# 770LCM.net
KiCad netlist of a schematic drawn in EAGLE
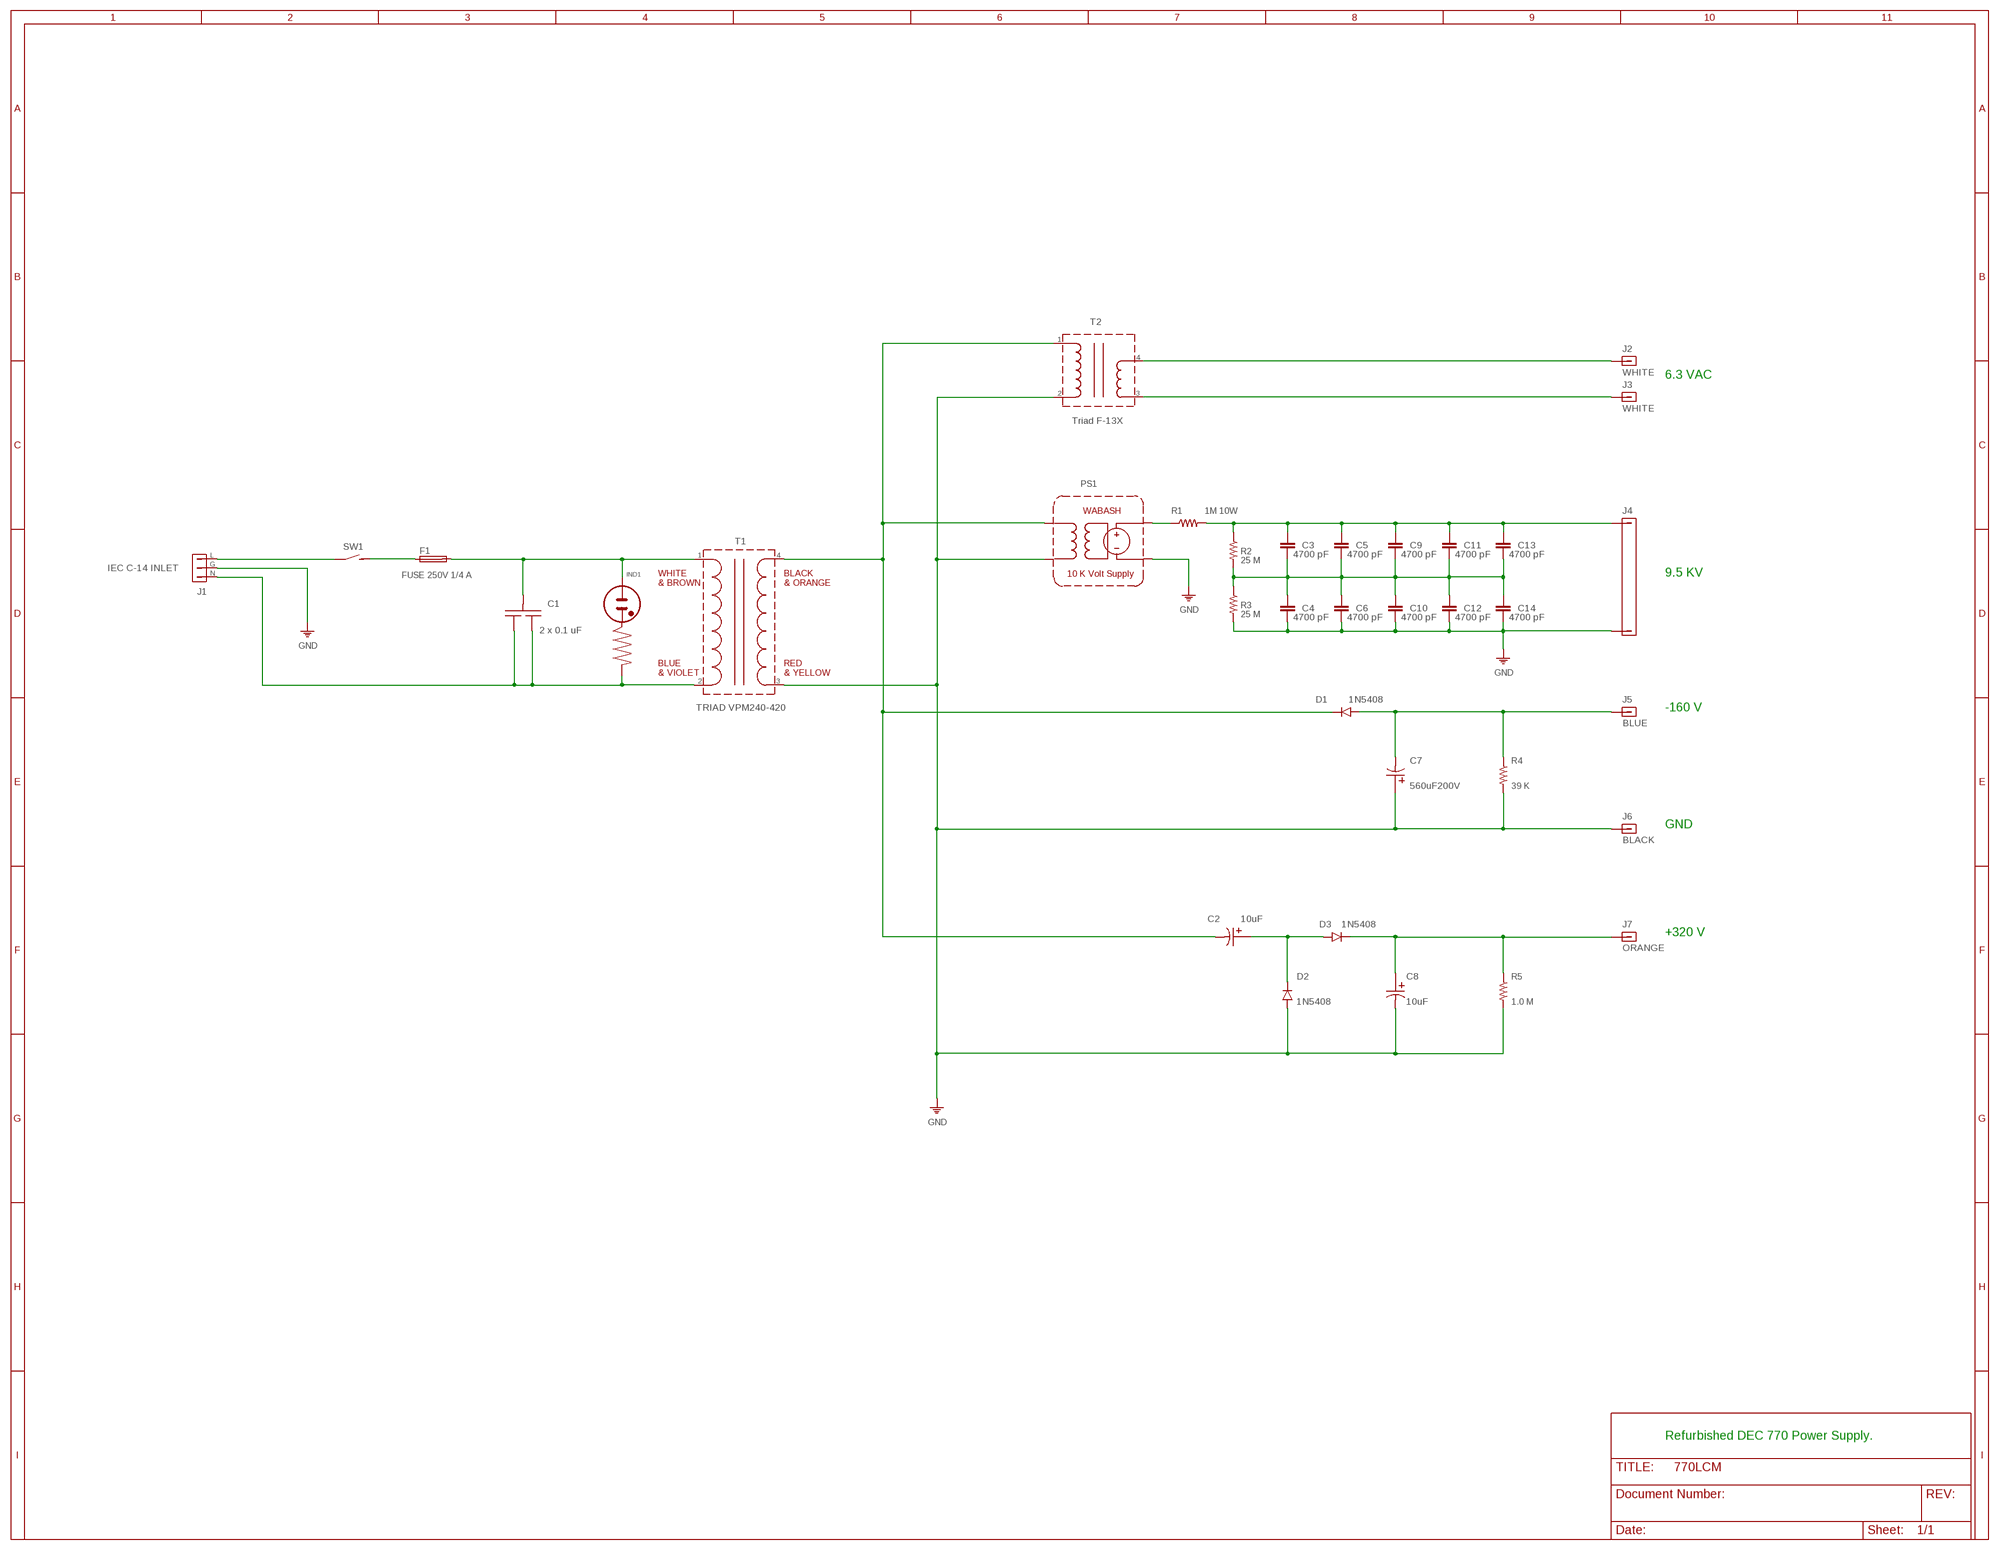
[diagram p0: schematic, sheet 1]

(export (version "E")
  (design (tool "Eeschema 10.0.6"))
  (components
    (comp (ref "C1")
      (value "2 x 0.1 uF")
      (footprint "eagle-import:THREE-PIN")
      (libsource (lib "eagle-import") (part "SPLIT-CAP"))
    )
    (comp (ref "C2")
      (value "10uF")
      (footprint "eagle-import:AXIAL10UF400V")
      (libsource (lib "eagle-import") (part "CAP400V10UF"))
    )
    (comp (ref "C3")
      (value "4700 pF")
      (footprint "eagle-import:C2.5")
      (libsource (lib "eagle-import") (part "C-0.1"))
    )
    (comp (ref "C4")
      (value "4700 pF")
      (footprint "eagle-import:C2.5")
      (libsource (lib "eagle-import") (part "C-0.1"))
    )
    (comp (ref "C5")
      (value "4700 pF")
      (footprint "eagle-import:C2.5")
      (libsource (lib "eagle-import") (part "C-0.1"))
    )
    (comp (ref "C6")
      (value "4700 pF")
      (footprint "eagle-import:C2.5")
      (libsource (lib "eagle-import") (part "C-0.1"))
    )
    (comp (ref "C7")
      (value "560uF200V")
      (footprint "eagle-import:WIREDCAP")
      (libsource (lib "eagle-import") (part "WIREDCAP"))
    )
    (comp (ref "C8")
      (value "10uF")
      (footprint "eagle-import:AXIAL10UF400V")
      (libsource (lib "eagle-import") (part "CAP400V10UF"))
    )
    (comp (ref "C9")
      (value "4700 pF")
      (footprint "eagle-import:C2.5")
      (libsource (lib "eagle-import") (part "C-0.1"))
    )
    (comp (ref "C10")
      (value "4700 pF")
      (footprint "eagle-import:C2.5")
      (libsource (lib "eagle-import") (part "C-0.1"))
    )
    (comp (ref "C11")
      (value "4700 pF")
      (footprint "eagle-import:C2.5")
      (libsource (lib "eagle-import") (part "C-0.1"))
    )
    (comp (ref "C12")
      (value "4700 pF")
      (footprint "eagle-import:C2.5")
      (libsource (lib "eagle-import") (part "C-0.1"))
    )
    (comp (ref "C13")
      (value "4700 pF")
      (footprint "eagle-import:C2.5")
      (libsource (lib "eagle-import") (part "C-0.1"))
    )
    (comp (ref "C14")
      (value "4700 pF")
      (footprint "eagle-import:C2.5")
      (libsource (lib "eagle-import") (part "C-0.1"))
    )
    (comp (ref "D1")
      (value "1N5408")
      (footprint "eagle-import:DO-201AD")
      (libsource (lib "eagle-import") (part "1N5408"))
    )
    (comp (ref "D2")
      (value "1N5408")
      (footprint "eagle-import:DO-201AD")
      (libsource (lib "eagle-import") (part "1N5408"))
    )
    (comp (ref "D3")
      (value "1N5408")
      (footprint "eagle-import:DO-201AD")
      (libsource (lib "eagle-import") (part "1N5408"))
    )
    (comp (ref "F1")
      (value "FUSE 250V 1/4 A")
      (footprint "eagle-import:FUSE_HOLDER_SCHURTER-FAS")
      (fields (field (name "MPN") "0031.3501"))
      (libsource (lib "eagle-import") (part "FUSEFAS"))
    )
    (comp (ref "IND1")
      (value "NEON_INDICATOR")
      (footprint "eagle-import:TWO-PIN")
      (libsource (lib "eagle-import") (part "NEON_INDICATOR"))
    )
    (comp (ref "J1")
      (value "IEC C-14 INLET")
      (footprint "eagle-import:IEC_CONNECTOR")
      (libsource (lib "eagle-import") (part "IEC-C14"))
    )
    (comp (ref "J2")
      (value "WHITE")
      (footprint "eagle-import:AWG18")
      (libsource (lib "eagle-import") (part "BANANA_JACK"))
    )
    (comp (ref "J3")
      (value "WHITE")
      (footprint "eagle-import:AWG18")
      (libsource (lib "eagle-import") (part "BANANA_JACK"))
    )
    (comp (ref "J4")
      (value "HV_CONN")
      (footprint "eagle-import:TWO-PIN")
      (libsource (lib "eagle-import") (part "HV_CONN"))
    )
    (comp (ref "J5")
      (value "BLUE")
      (footprint "eagle-import:AWG18")
      (libsource (lib "eagle-import") (part "BANANA_JACK"))
    )
    (comp (ref "J6")
      (value "BLACK")
      (footprint "eagle-import:AWG18")
      (libsource (lib "eagle-import") (part "BANANA_JACK"))
    )
    (comp (ref "J7")
      (value "ORANGE")
      (footprint "eagle-import:AWG18")
      (libsource (lib "eagle-import") (part "BANANA_JACK"))
    )
    (comp (ref "PS1")
      (value "WABASH-HV")
      (footprint "eagle-import:TRANSFORMER")
      (libsource (lib "eagle-import") (part "WABASH-HV"))
    )
    (comp (ref "R1")
      (value "1M 10W")
      (footprint "eagle-import:0207_10")
      (libsource (lib "eagle-import") (part "RES-H"))
    )
    (comp (ref "R2")
      (value "25 M")
      (footprint "eagle-import:0207_10")
      (libsource (lib "eagle-import") (part "RES-V"))
    )
    (comp (ref "R3")
      (value "25 M")
      (footprint "eagle-import:0207_10")
      (libsource (lib "eagle-import") (part "RES-V"))
    )
    (comp (ref "R4")
      (value "39 K")
      (footprint "eagle-import:0207_10")
      (libsource (lib "eagle-import") (part "RES-V"))
    )
    (comp (ref "R5")
      (value "1.0 M")
      (footprint "eagle-import:0207_10")
      (libsource (lib "eagle-import") (part "RES-V"))
    )
    (comp (ref "SW1")
      (value "SWITCH")
      (footprint "eagle-import:SWITCH")
      (libsource (lib "eagle-import") (part "SWITCH"))
    )
    (comp (ref "T1")
      (value "TRIAD VPM240-420")
      (footprint "eagle-import:TRANSFORMER")
      (libsource (lib "eagle-import") (part "TRANSFORMER"))
    )
    (comp (ref "T2")
      (value "Triad F-13X")
      (footprint "eagle-import:TRANSFORMER")
      (libsource (lib "eagle-import") (part "SMALLTRANSFORMER"))
    )
  )
  (nets
    (net (code "1") (name "GND") (class "Default")
      (node (ref "C10") (pin "2") (pinfunction "2_2") (pintype "passive"))
      (node (ref "C12") (pin "2") (pinfunction "2_2") (pintype "passive"))
      (node (ref "C14") (pin "2") (pinfunction "2_2") (pintype "passive"))
      (node (ref "C4") (pin "2") (pinfunction "2_2") (pintype "passive"))
      (node (ref "C6") (pin "2") (pinfunction "2_2") (pintype "passive"))
      (node (ref "C7") (pin "P$1") (pinfunction "1_P$1") (pintype "passive"))
      (node (ref "C8") (pin "P$2") (pinfunction "2_P$2") (pintype "passive"))
      (node (ref "D2") (pin "A") (pinfunction "A_A") (pintype "passive"))
      (node (ref "J1") (pin "G") (pinfunction "G_G") (pintype "passive"))
      (node (ref "J4") (pin "P$2") (pinfunction "L1_P$2") (pintype "passive"))
      (node (ref "J6") (pin "P$1") (pinfunction "L1_P$1") (pintype "passive"))
      (node (ref "PS1") (pin "2") (pinfunction "AC2_2") (pintype "passive"))
      (node (ref "PS1") (pin "3") (pinfunction "GND_3") (pintype "passive"))
      (node (ref "R3") (pin "2") (pinfunction "P$2_2") (pintype "passive"))
      (node (ref "R4") (pin "2") (pinfunction "P$2_2") (pintype "passive"))
      (node (ref "R5") (pin "2") (pinfunction "P$2_2") (pintype "passive"))
      (node (ref "T1") (pin "3") (pinfunction "3_3") (pintype "bidirectional"))
      (node (ref "T2") (pin "2") (pinfunction "2_2") (pintype "bidirectional"))
    )
    (net (code "2") (name "Net-(C1-1)") (class "Default")
      (node (ref "C1") (pin "P$1") (pinfunction "1_P$1") (pintype "passive"))
      (node (ref "C1") (pin "P$2") (pinfunction "2_P$2") (pintype "passive"))
      (node (ref "IND1") (pin "P$2") (pinfunction "A1_P$2") (pintype "passive"))
      (node (ref "J1") (pin "N") (pinfunction "L_N") (pintype "passive"))
      (node (ref "T1") (pin "2") (pinfunction "2_2") (pintype "bidirectional"))
    )
    (net (code "3") (name "Net-(C1-3)") (class "Default")
      (node (ref "C1") (pin "P$3") (pinfunction "3_P$3") (pintype "passive"))
      (node (ref "F1") (pin "B") (pinfunction "2_B") (pintype "passive"))
      (node (ref "IND1") (pin "P$1") (pinfunction "A_P$1") (pintype "passive"))
      (node (ref "T1") (pin "1") (pinfunction "1_1") (pintype "bidirectional"))
    )
    (net (code "4") (name "Net-(C2-1)") (class "Default")
      (node (ref "C2") (pin "P$1") (pinfunction "1_P$1") (pintype "passive"))
      (node (ref "D2") (pin "C") (pinfunction "C_C") (pintype "passive"))
      (node (ref "D3") (pin "A") (pinfunction "A_A") (pintype "passive"))
    )
    (net (code "5") (name "Net-(C2-2)") (class "Default")
      (node (ref "C2") (pin "P$2") (pinfunction "2_P$2") (pintype "passive"))
      (node (ref "D1") (pin "C") (pinfunction "C_C") (pintype "passive"))
      (node (ref "PS1") (pin "1") (pinfunction "AC1_1") (pintype "passive"))
      (node (ref "T1") (pin "4") (pinfunction "4_4") (pintype "bidirectional"))
      (node (ref "T2") (pin "1") (pinfunction "1_1") (pintype "bidirectional"))
    )
    (net (code "6") (name "Net-(C7-2)") (class "Default")
      (node (ref "C7") (pin "P$2") (pinfunction "2_P$2") (pintype "passive"))
      (node (ref "D1") (pin "A") (pinfunction "A_A") (pintype "passive"))
      (node (ref "J5") (pin "P$1") (pinfunction "L1_P$1") (pintype "passive"))
      (node (ref "R4") (pin "1") (pinfunction "P$1_1") (pintype "passive"))
    )
    (net (code "7") (name "Net-(C8-1)") (class "Default")
      (node (ref "C8") (pin "P$1") (pinfunction "1_P$1") (pintype "passive"))
      (node (ref "D3") (pin "C") (pinfunction "C_C") (pintype "passive"))
      (node (ref "J7") (pin "P$1") (pinfunction "L1_P$1") (pintype "passive"))
      (node (ref "R5") (pin "1") (pinfunction "P$1_1") (pintype "passive"))
    )
    (net (code "8") (name "Net-(F1-1)") (class "Default")
      (node (ref "F1") (pin "A") (pinfunction "1_A") (pintype "passive"))
      (node (ref "SW1") (pin "P$2") (pinfunction "S_P$2") (pintype "passive"))
    )
    (net (code "9") (name "Net-(J1-N)") (class "Default")
      (node (ref "J1") (pin "L") (pinfunction "N_L") (pintype "passive"))
      (node (ref "SW1") (pin "P$1") (pinfunction "P_P$1") (pintype "passive"))
    )
    (net (code "10") (name "Net-(J2-L1)") (class "Default")
      (node (ref "J2") (pin "P$1") (pinfunction "L1_P$1") (pintype "passive"))
      (node (ref "T2") (pin "4") (pinfunction "4_4") (pintype "bidirectional"))
    )
    (net (code "11") (name "Net-(J3-L1)") (class "Default")
      (node (ref "J3") (pin "P$1") (pinfunction "L1_P$1") (pintype "passive"))
      (node (ref "T2") (pin "3") (pinfunction "3_3") (pintype "bidirectional"))
    )
    (net (code "12") (name "Net-(J4-L)") (class "Default")
      (node (ref "C11") (pin "1") (pinfunction "1_1") (pintype "passive"))
      (node (ref "C13") (pin "1") (pinfunction "1_1") (pintype "passive"))
      (node (ref "C3") (pin "1") (pinfunction "1_1") (pintype "passive"))
      (node (ref "C5") (pin "1") (pinfunction "1_1") (pintype "passive"))
      (node (ref "C9") (pin "1") (pinfunction "1_1") (pintype "passive"))
      (node (ref "J4") (pin "P$1") (pinfunction "L_P$1") (pintype "passive"))
      (node (ref "R1") (pin "2") (pinfunction "P$2_2") (pintype "passive"))
      (node (ref "R2") (pin "1") (pinfunction "P$1_1") (pintype "passive"))
    )
    (net (code "13") (name "Net-(PS1-HV)") (class "Default")
      (node (ref "PS1") (pin "4") (pinfunction "HV_4") (pintype "passive"))
      (node (ref "R1") (pin "1") (pinfunction "P$1_1") (pintype "passive"))
    )
    (net (code "14") (name "Net-(R2-P$2)") (class "Default")
      (node (ref "C10") (pin "1") (pinfunction "1_1") (pintype "passive"))
      (node (ref "C11") (pin "2") (pinfunction "2_2") (pintype "passive"))
      (node (ref "C12") (pin "1") (pinfunction "1_1") (pintype "passive"))
      (node (ref "C13") (pin "2") (pinfunction "2_2") (pintype "passive"))
      (node (ref "C14") (pin "1") (pinfunction "1_1") (pintype "passive"))
      (node (ref "C3") (pin "2") (pinfunction "2_2") (pintype "passive"))
      (node (ref "C4") (pin "1") (pinfunction "1_1") (pintype "passive"))
      (node (ref "C5") (pin "2") (pinfunction "2_2") (pintype "passive"))
      (node (ref "C6") (pin "1") (pinfunction "1_1") (pintype "passive"))
      (node (ref "C9") (pin "2") (pinfunction "2_2") (pintype "passive"))
      (node (ref "R2") (pin "2") (pinfunction "P$2_2") (pintype "passive"))
      (node (ref "R3") (pin "1") (pinfunction "P$1_1") (pintype "passive"))
    )
  )
)
